# GH_Terra_pre.net
KiCad netlist of a schematic drawn in EAGLE
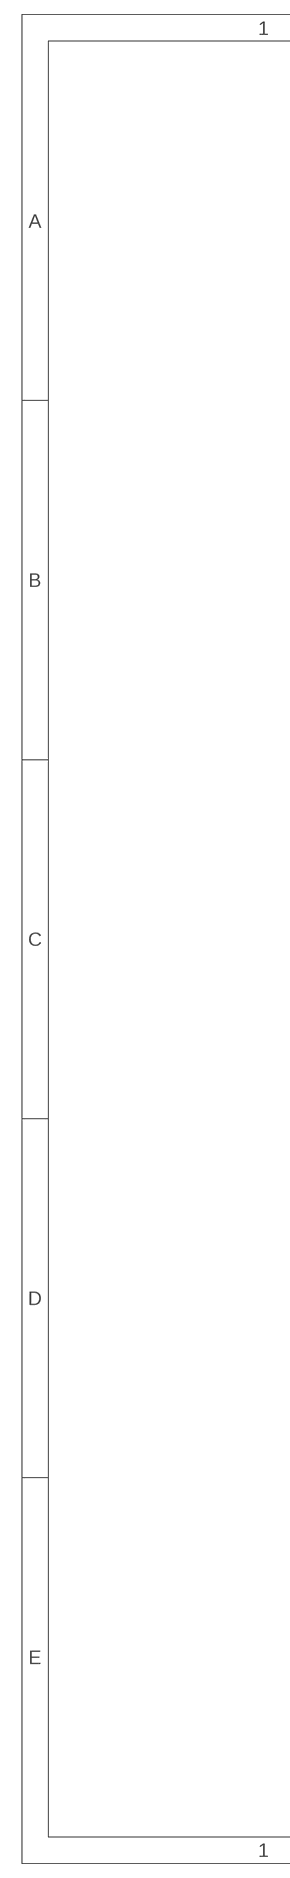
[diagram p0: schematic, sheet 1, part 1 of 2]
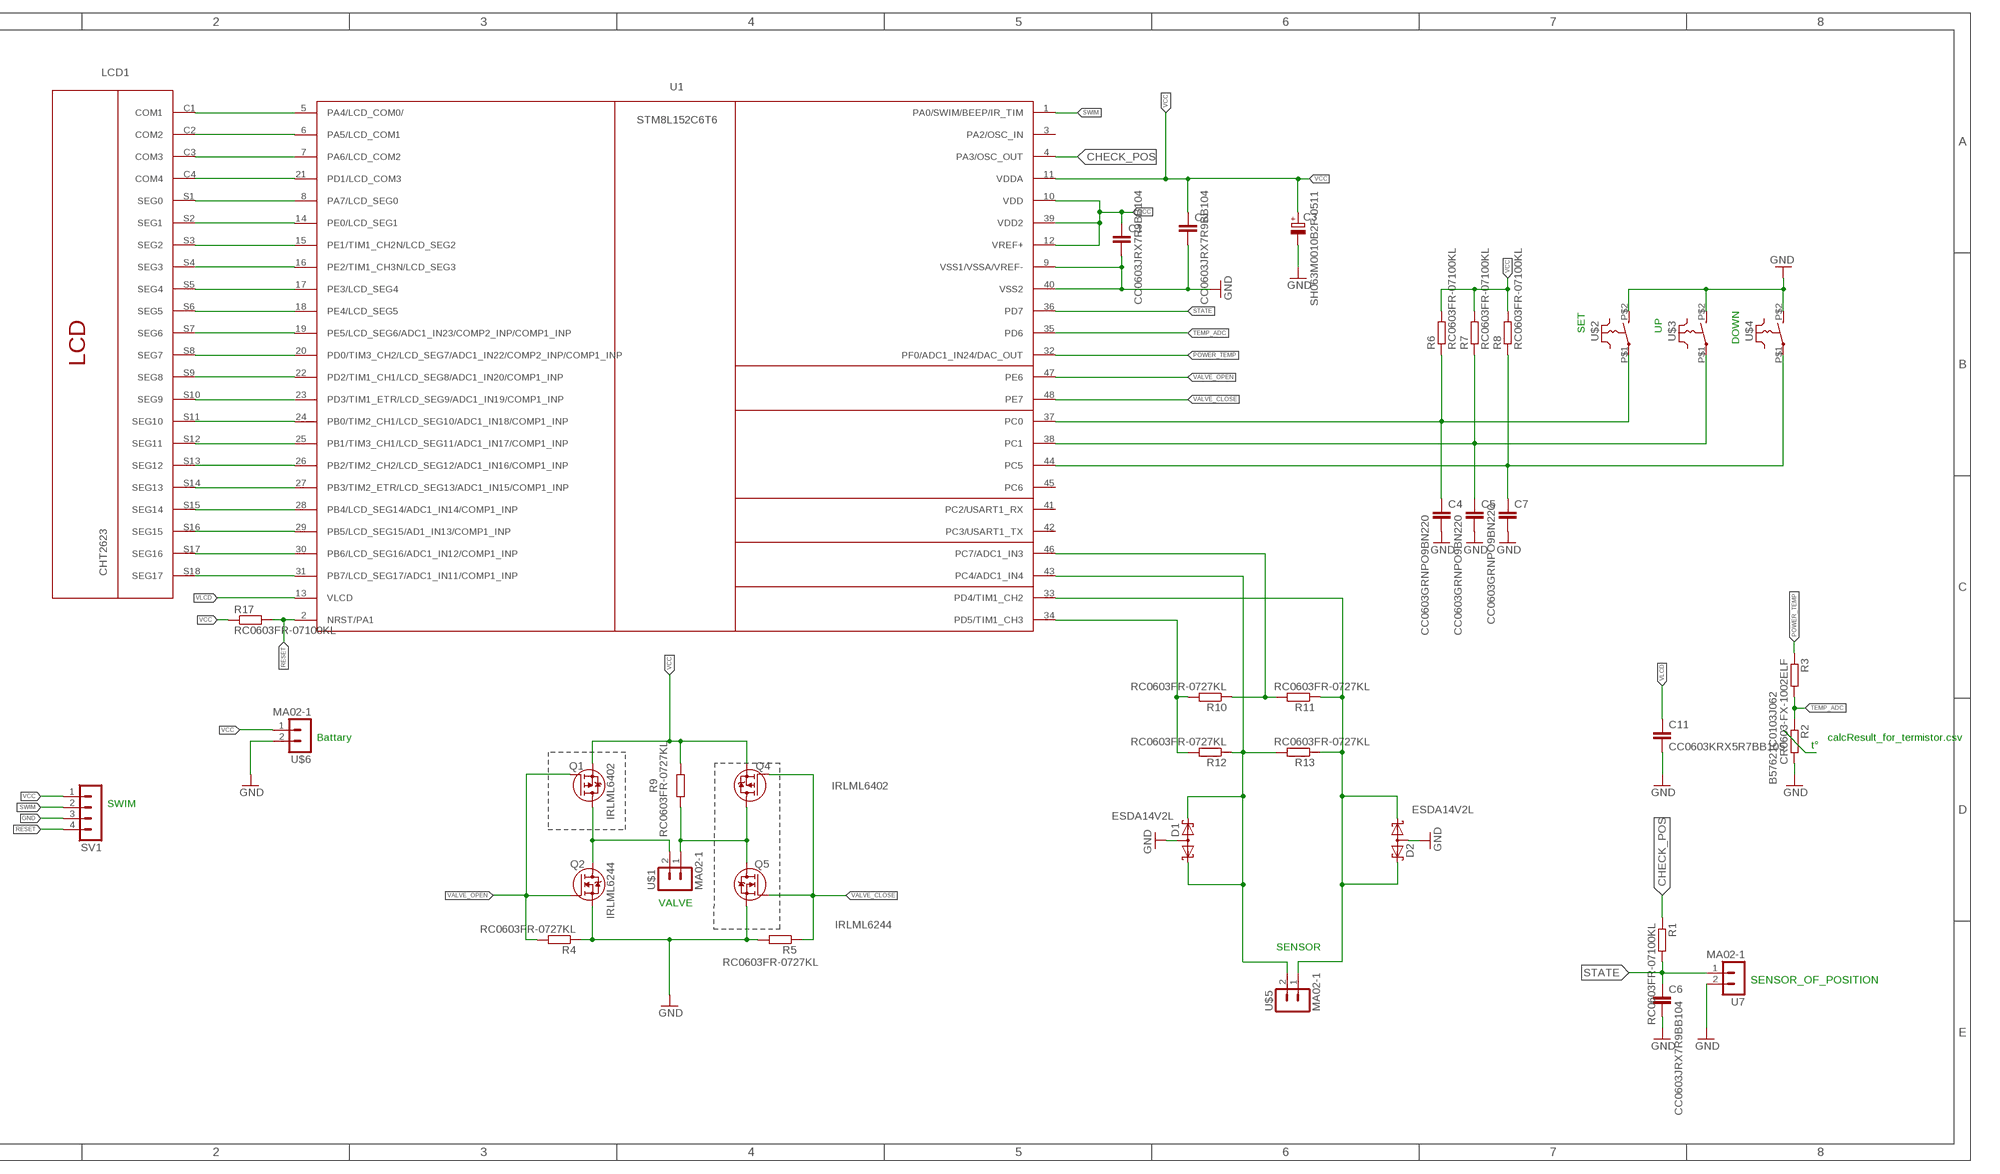
[diagram p1: schematic, sheet 1, part 2 of 2]

(export (version "E")
  (design (tool "Eeschema 10.0.6"))
  (components
    (comp (ref "C1")
      (value "CC0603JRX7R9BB104")
      (footprint "eagle-import:C0603_IPC")
      (libsource (lib "eagle-import") (part "C-EUC0603"))
    )
    (comp (ref "C2")
      (value "CC0603JRX7R9BB104")
      (footprint "eagle-import:C0603_IPC")
      (libsource (lib "eagle-import") (part "C-EUC0603"))
    )
    (comp (ref "C3")
      (value "SH063M0010B2F-0511")
      (footprint "eagle-import:SANYO-OSCON_C6")
      (libsource (lib "eagle-import") (part "CPOL-EUSANYO_C6"))
    )
    (comp (ref "C4")
      (value "CC0603GRNPO9BN220")
      (footprint "eagle-import:C0603_IPC")
      (libsource (lib "eagle-import") (part "C-EUC0603"))
    )
    (comp (ref "C5")
      (value "CC0603GRNPO9BN220")
      (footprint "eagle-import:C0603_IPC")
      (libsource (lib "eagle-import") (part "C-EUC0603"))
    )
    (comp (ref "C6")
      (value "CC0603JRX7R9BB104")
      (footprint "eagle-import:C0603_IPC")
      (libsource (lib "eagle-import") (part "C-EUC0603"))
    )
    (comp (ref "C7")
      (value "CC0603GRNPO9BN220")
      (footprint "eagle-import:C0603_IPC")
      (libsource (lib "eagle-import") (part "C-EUC0603"))
    )
    (comp (ref "C11")
      (value "CC0603KRX5R7BB105")
      (footprint "eagle-import:C0603_IPC")
      (libsource (lib "eagle-import") (part "C-EUC0603"))
    )
    (comp (ref "D1")
      (value "ESDA14V2L")
      (footprint "eagle-import:SOT23")
      (libsource (lib "eagle-import") (part "BAS40-06"))
    )
    (comp (ref "D2")
      (value "ESDA14V2L")
      (footprint "eagle-import:SOT23")
      (libsource (lib "eagle-import") (part "BAS40-06"))
    )
    (comp (ref "LCD1")
      (value "CHT2623")
      (footprint "eagle-import:CHT2623")
      (libsource (lib "eagle-import") (part "CHT2623"))
    )
    (comp (ref "Q1")
      (value "IRLML6402")
      (footprint "eagle-import:SOT23")
      (libsource (lib "eagle-import") (part "PFET-SOT23"))
    )
    (comp (ref "Q2")
      (value "IRLML6244")
      (footprint "eagle-import:SOT23")
      (libsource (lib "eagle-import") (part "NFET-SOT23"))
    )
    (comp (ref "Q4")
      (value "IRLML6402")
      (footprint "eagle-import:SOT23")
      (libsource (lib "eagle-import") (part "PFET-SOT23"))
    )
    (comp (ref "Q5")
      (value "IRLML6244")
      (footprint "eagle-import:SOT23")
      (libsource (lib "eagle-import") (part "NFET-SOT23"))
    )
    (comp (ref "R1")
      (value "RC0603FR-07100KL")
      (footprint "eagle-import:R0603_IPC")
      (libsource (lib "eagle-import") (part "R-EU_R0603"))
    )
    (comp (ref "R2")
      (value "B57621C0103J062")
      (footprint "eagle-import:R1206")
      (libsource (lib "eagle-import") (part "R-EU_R1206"))
    )
    (comp (ref "R3")
      (value "CR0603-FX-1002ELF")
      (footprint "eagle-import:R0603_IPC")
      (libsource (lib "eagle-import") (part "R-EU_R0603"))
    )
    (comp (ref "R4")
      (value "RC0603FR-0727KL")
      (footprint "eagle-import:R0603_IPC")
      (libsource (lib "eagle-import") (part "R-EU_R0603"))
    )
    (comp (ref "R5")
      (value "RC0603FR-0727KL")
      (footprint "eagle-import:R0603_IPC")
      (libsource (lib "eagle-import") (part "R-EU_R0603"))
    )
    (comp (ref "R6")
      (value "RC0603FR-07100KL")
      (footprint "eagle-import:R0603_IPC")
      (libsource (lib "eagle-import") (part "R-EU_R0603"))
    )
    (comp (ref "R7")
      (value "RC0603FR-07100KL")
      (footprint "eagle-import:R0603_IPC")
      (libsource (lib "eagle-import") (part "R-EU_R0603"))
    )
    (comp (ref "R8")
      (value "RC0603FR-07100KL")
      (footprint "eagle-import:R0603_IPC")
      (libsource (lib "eagle-import") (part "R-EU_R0603"))
    )
    (comp (ref "R9")
      (value "RC0603FR-0727KL")
      (footprint "eagle-import:R0603_IPC")
      (libsource (lib "eagle-import") (part "R-EU_R0603"))
    )
    (comp (ref "R10")
      (value "RC0603FR-0727KL")
      (footprint "eagle-import:R0603_IPC")
      (libsource (lib "eagle-import") (part "R-EU_R0603"))
    )
    (comp (ref "R11")
      (value "RC0603FR-0727KL")
      (footprint "eagle-import:R0603_IPC")
      (libsource (lib "eagle-import") (part "R-EU_R0603"))
    )
    (comp (ref "R12")
      (value "RC0603FR-0727KL")
      (footprint "eagle-import:R0603_IPC")
      (libsource (lib "eagle-import") (part "R-EU_R0603"))
    )
    (comp (ref "R13")
      (value "RC0603FR-0727KL")
      (footprint "eagle-import:R0603_IPC")
      (libsource (lib "eagle-import") (part "R-EU_R0603"))
    )
    (comp (ref "R17")
      (value "RC0603FR-07100KL")
      (footprint "eagle-import:R0603_IPC")
      (libsource (lib "eagle-import") (part "R-EU_R0603"))
    )
    (comp (ref "SV1")
      (value "MA04-1")
      (footprint "eagle-import:MA04-1")
      (libsource (lib "eagle-import") (part "MA04-1"))
    )
    (comp (ref "U$1")
      (value "MA02-1")
      (footprint "eagle-import:MA02-1")
      (libsource (lib "eagle-import") (part "MA02-1"))
    )
    (comp (ref "U$2")
      (value "RK_4X3")
      (footprint "eagle-import:RK_3X4")
      (libsource (lib "eagle-import") (part "RK_4X3"))
    )
    (comp (ref "U$3")
      (value "RK_4X3")
      (footprint "eagle-import:RK_3X4")
      (libsource (lib "eagle-import") (part "RK_4X3"))
    )
    (comp (ref "U$4")
      (value "RK_4X3")
      (footprint "eagle-import:RK_3X4")
      (libsource (lib "eagle-import") (part "RK_4X3"))
    )
    (comp (ref "U$5")
      (value "MA02-1")
      (footprint "eagle-import:MA02-1")
      (libsource (lib "eagle-import") (part "MA02-1"))
    )
    (comp (ref "U$6")
      (value "MA02-1")
      (footprint "eagle-import:MA02-1")
      (libsource (lib "eagle-import") (part "MA02-1"))
    )
    (comp (ref "U1")
      (value "STM8L152C6T6")
      (footprint "eagle-import:LQFP48")
      (libsource (lib "eagle-import") (part "STM8L152C6"))
    )
    (comp (ref "U7")
      (value "MA02-1")
      (footprint "eagle-import:MA02-1")
      (libsource (lib "eagle-import") (part "MA02-1"))
    )
  )
  (nets
    (net (code "1") (name "CHECK_POS") (class "Default")
      (node (ref "R1") (pin "1") (pinfunction "1_1") (pintype "passive"))
      (node (ref "U1") (pin "4") (pinfunction "PA3/OSC_OUT_4") (pintype "bidirectional"))
    )
    (net (code "2") (name "GND") (class "Default")
      (node (ref "C1") (pin "2") (pinfunction "2_2") (pintype "passive"))
      (node (ref "C11") (pin "2") (pinfunction "2_2") (pintype "passive"))
      (node (ref "C2") (pin "2") (pinfunction "2_2") (pintype "passive"))
      (node (ref "C3") (pin "-") (pinfunction "-_-") (pintype "passive"))
      (node (ref "C4") (pin "2") (pinfunction "2_2") (pintype "passive"))
      (node (ref "C5") (pin "2") (pinfunction "2_2") (pintype "passive"))
      (node (ref "C6") (pin "2") (pinfunction "2_2") (pintype "passive"))
      (node (ref "C7") (pin "2") (pinfunction "2_2") (pintype "passive"))
      (node (ref "D1") (pin "3") (pinfunction "AA_3") (pintype "passive"))
      (node (ref "D2") (pin "3") (pinfunction "AA_3") (pintype "passive"))
      (node (ref "Q2") (pin "2") (pinfunction "S_2") (pintype "passive"))
      (node (ref "Q5") (pin "2") (pinfunction "S_2") (pintype "passive"))
      (node (ref "R2") (pin "2") (pinfunction "2_2") (pintype "passive"))
      (node (ref "R4") (pin "1") (pinfunction "1_1") (pintype "passive"))
      (node (ref "R5") (pin "2") (pinfunction "2_2") (pintype "passive"))
      (node (ref "SV1") (pin "3") (pinfunction "3_3") (pintype "passive"))
      (node (ref "U$2") (pin "P$2") (pinfunction "S_P$2") (pintype "passive"))
      (node (ref "U$3") (pin "P$2") (pinfunction "S_P$2") (pintype "passive"))
      (node (ref "U$4") (pin "P$2") (pinfunction "S_P$2") (pintype "passive"))
      (node (ref "U$6") (pin "2") (pinfunction "2_2") (pintype "passive"))
      (node (ref "U1") (pin "40") (pinfunction "VSS2_40") (pintype "bidirectional"))
      (node (ref "U1") (pin "9") (pinfunction "VSS1/VSSA/VREF-_9") (pintype "bidirectional"))
      (node (ref "U7") (pin "2") (pinfunction "2_2") (pintype "passive"))
    )
    (net (code "3") (name "Net-(D1-K1)") (class "Default")
      (node (ref "D1") (pin "1") (pinfunction "K1_1") (pintype "passive"))
      (node (ref "D1") (pin "2") (pinfunction "K2_2") (pintype "passive"))
      (node (ref "R12") (pin "1") (pinfunction "1_1") (pintype "passive"))
      (node (ref "R13") (pin "2") (pinfunction "2_2") (pintype "passive"))
      (node (ref "U$5") (pin "2") (pinfunction "2_2") (pintype "passive"))
      (node (ref "U1") (pin "43") (pinfunction "PC4/ADC1_IN4_43") (pintype "bidirectional"))
    )
    (net (code "4") (name "Net-(D2-K1)") (class "Default")
      (node (ref "D2") (pin "1") (pinfunction "K1_1") (pintype "passive"))
      (node (ref "D2") (pin "2") (pinfunction "K2_2") (pintype "passive"))
      (node (ref "R11") (pin "1") (pinfunction "1_1") (pintype "passive"))
      (node (ref "R13") (pin "1") (pinfunction "1_1") (pintype "passive"))
      (node (ref "U$5") (pin "1") (pinfunction "1_1") (pintype "passive"))
      (node (ref "U1") (pin "33") (pinfunction "PD4/TIM1_CH2_33") (pintype "bidirectional"))
    )
    (net (code "5") (name "Net-(LCD1-COM1)") (class "Default")
      (node (ref "LCD1") (pin "C1") (pinfunction "COM1_C1") (pintype "bidirectional"))
      (node (ref "U1") (pin "5") (pinfunction "PA4/LCD_COM0/_5") (pintype "bidirectional"))
    )
    (net (code "6") (name "Net-(LCD1-COM2)") (class "Default")
      (node (ref "LCD1") (pin "C2") (pinfunction "COM2_C2") (pintype "bidirectional"))
      (node (ref "U1") (pin "6") (pinfunction "PA5/LCD_COM1_6") (pintype "bidirectional"))
    )
    (net (code "7") (name "Net-(LCD1-COM3)") (class "Default")
      (node (ref "LCD1") (pin "C3") (pinfunction "COM3_C3") (pintype "bidirectional"))
      (node (ref "U1") (pin "7") (pinfunction "PA6/LCD_COM2_7") (pintype "bidirectional"))
    )
    (net (code "8") (name "Net-(LCD1-COM4)") (class "Default")
      (node (ref "LCD1") (pin "C4") (pinfunction "COM4_C4") (pintype "bidirectional"))
      (node (ref "U1") (pin "21") (pinfunction "PD1/LCD_COM3_21") (pintype "bidirectional"))
    )
    (net (code "9") (name "Net-(LCD1-SEG0)") (class "Default")
      (node (ref "LCD1") (pin "S1") (pinfunction "SEG0_S1") (pintype "bidirectional"))
      (node (ref "U1") (pin "8") (pinfunction "PA7/LCD_SEG0_8") (pintype "bidirectional"))
    )
    (net (code "10") (name "Net-(LCD1-SEG1)") (class "Default")
      (node (ref "LCD1") (pin "S2") (pinfunction "SEG1_S2") (pintype "bidirectional"))
      (node (ref "U1") (pin "14") (pinfunction "PE0/LCD_SEG1_14") (pintype "bidirectional"))
    )
    (net (code "11") (name "Net-(LCD1-SEG2)") (class "Default")
      (node (ref "LCD1") (pin "S3") (pinfunction "SEG2_S3") (pintype "bidirectional"))
      (node (ref "U1") (pin "15") (pinfunction "PE1/TIM1_CH2N/LCD_SEG2_15") (pintype "bidirectional"))
    )
    (net (code "12") (name "Net-(LCD1-SEG3)") (class "Default")
      (node (ref "LCD1") (pin "S4") (pinfunction "SEG3_S4") (pintype "bidirectional"))
      (node (ref "U1") (pin "16") (pinfunction "PE2/TIM1_CH3N/LCD_SEG3_16") (pintype "bidirectional"))
    )
    (net (code "13") (name "Net-(LCD1-SEG4)") (class "Default")
      (node (ref "LCD1") (pin "S5") (pinfunction "SEG4_S5") (pintype "bidirectional"))
      (node (ref "U1") (pin "17") (pinfunction "PE3/LCD_SEG4_17") (pintype "bidirectional"))
    )
    (net (code "14") (name "Net-(LCD1-SEG5)") (class "Default")
      (node (ref "LCD1") (pin "S6") (pinfunction "SEG5_S6") (pintype "bidirectional"))
      (node (ref "U1") (pin "18") (pinfunction "PE4/LCD_SEG5_18") (pintype "bidirectional"))
    )
    (net (code "15") (name "Net-(LCD1-SEG6)") (class "Default")
      (node (ref "LCD1") (pin "S7") (pinfunction "SEG6_S7") (pintype "bidirectional"))
      (node (ref "U1") (pin "19") (pinfunction "PE5/LCD_SEG6/ADC1_IN23/COMP2_INP/COMP1_INP_19") (pintype "bidirectional"))
    )
    (net (code "16") (name "Net-(LCD1-SEG7)") (class "Default")
      (node (ref "LCD1") (pin "S8") (pinfunction "SEG7_S8") (pintype "bidirectional"))
      (node (ref "U1") (pin "20") (pinfunction "PD0/TIM3_CH2/LCD_SEG7/ADC1_IN22/COMP2_INP/COMP1_INP_20") (pintype "bidirectional"))
    )
    (net (code "17") (name "Net-(LCD1-SEG8)") (class "Default")
      (node (ref "LCD1") (pin "S9") (pinfunction "SEG8_S9") (pintype "bidirectional"))
      (node (ref "U1") (pin "22") (pinfunction "PD2/TIM1_CH1/LCD_SEG8/ADC1_IN20/COMP1_INP_22") (pintype "bidirectional"))
    )
    (net (code "18") (name "Net-(LCD1-SEG9)") (class "Default")
      (node (ref "LCD1") (pin "S10") (pinfunction "SEG9_S10") (pintype "bidirectional"))
      (node (ref "U1") (pin "23") (pinfunction "PD3/TIM1_ETR/LCD_SEG9/ADC1_IN19/COMP1_INP_23") (pintype "bidirectional"))
    )
    (net (code "19") (name "Net-(LCD1-SEG10)") (class "Default")
      (node (ref "LCD1") (pin "S11") (pinfunction "SEG10_S11") (pintype "bidirectional"))
      (node (ref "U1") (pin "24") (pinfunction "PB0/TIM2_CH1/LCD_SEG10/ADC1_IN18/COMP1_INP_24") (pintype "bidirectional"))
    )
    (net (code "20") (name "Net-(LCD1-SEG11)") (class "Default")
      (node (ref "LCD1") (pin "S12") (pinfunction "SEG11_S12") (pintype "bidirectional"))
      (node (ref "U1") (pin "25") (pinfunction "PB1/TIM3_CH1/LCD_SEG11/ADC1_IN17/COMP1_INP_25") (pintype "bidirectional"))
    )
    (net (code "21") (name "Net-(LCD1-SEG12)") (class "Default")
      (node (ref "LCD1") (pin "S13") (pinfunction "SEG12_S13") (pintype "bidirectional"))
      (node (ref "U1") (pin "26") (pinfunction "PB2/TIM2_CH2/LCD_SEG12/ADC1_IN16/COMP1_INP_26") (pintype "bidirectional"))
    )
    (net (code "22") (name "Net-(LCD1-SEG13)") (class "Default")
      (node (ref "LCD1") (pin "S14") (pinfunction "SEG13_S14") (pintype "bidirectional"))
      (node (ref "U1") (pin "27") (pinfunction "PB3/TIM2_ETR/LCD_SEG13/ADC1_IN15/COMP1_INP_27") (pintype "bidirectional"))
    )
    (net (code "23") (name "Net-(LCD1-SEG14)") (class "Default")
      (node (ref "LCD1") (pin "S15") (pinfunction "SEG14_S15") (pintype "bidirectional"))
      (node (ref "U1") (pin "28") (pinfunction "PB4/LCD_SEG14/ADC1_IN14/COMP1_INP_28") (pintype "bidirectional"))
    )
    (net (code "24") (name "Net-(LCD1-SEG15)") (class "Default")
      (node (ref "LCD1") (pin "S16") (pinfunction "SEG15_S16") (pintype "bidirectional"))
      (node (ref "U1") (pin "29") (pinfunction "PB5/LCD_SEG15/AD1_IN13/COMP1_INP_29") (pintype "bidirectional"))
    )
    (net (code "25") (name "Net-(LCD1-SEG16)") (class "Default")
      (node (ref "LCD1") (pin "S17") (pinfunction "SEG16_S17") (pintype "bidirectional"))
      (node (ref "U1") (pin "30") (pinfunction "PB6/LCD_SEG16/ADC1_IN12/COMP1_INP_30") (pintype "bidirectional"))
    )
    (net (code "26") (name "Net-(LCD1-SEG17)") (class "Default")
      (node (ref "LCD1") (pin "S18") (pinfunction "SEG17_S18") (pintype "bidirectional"))
      (node (ref "U1") (pin "31") (pinfunction "PB7/LCD_SEG17/ADC1_IN11/COMP1_INP_31") (pintype "bidirectional"))
    )
    (net (code "27") (name "Net-(Q1-D)") (class "Default")
      (node (ref "Q1") (pin "3") (pinfunction "D_3") (pintype "passive"))
      (node (ref "Q2") (pin "3") (pinfunction "D_3") (pintype "passive"))
      (node (ref "U$1") (pin "2") (pinfunction "2_2") (pintype "passive"))
    )
    (net (code "28") (name "Net-(Q4-D)") (class "Default")
      (node (ref "Q4") (pin "3") (pinfunction "D_3") (pintype "passive"))
      (node (ref "Q5") (pin "3") (pinfunction "D_3") (pintype "passive"))
      (node (ref "R9") (pin "2") (pinfunction "2_2") (pintype "passive"))
      (node (ref "U$1") (pin "1") (pinfunction "1_1") (pintype "passive"))
    )
    (net (code "29") (name "Net-(U$2-P)") (class "Default")
      (node (ref "C4") (pin "1") (pinfunction "1_1") (pintype "passive"))
      (node (ref "R6") (pin "1") (pinfunction "1_1") (pintype "passive"))
      (node (ref "U$2") (pin "P$1") (pinfunction "P_P$1") (pintype "passive"))
      (node (ref "U1") (pin "37") (pinfunction "PC0_37") (pintype "bidirectional"))
    )
    (net (code "30") (name "Net-(U$3-P)") (class "Default")
      (node (ref "C5") (pin "1") (pinfunction "1_1") (pintype "passive"))
      (node (ref "R7") (pin "1") (pinfunction "1_1") (pintype "passive"))
      (node (ref "U$3") (pin "P$1") (pinfunction "P_P$1") (pintype "passive"))
      (node (ref "U1") (pin "38") (pinfunction "PC1_38") (pintype "bidirectional"))
    )
    (net (code "31") (name "Net-(U$4-P)") (class "Default")
      (node (ref "C7") (pin "1") (pinfunction "1_1") (pintype "passive"))
      (node (ref "R8") (pin "1") (pinfunction "1_1") (pintype "passive"))
      (node (ref "U$4") (pin "P$1") (pinfunction "P_P$1") (pintype "passive"))
      (node (ref "U1") (pin "44") (pinfunction "PC5_44") (pintype "bidirectional"))
    )
    (net (code "32") (name "Net-(U1-PC7{slash}ADC1_IN3)") (class "Default")
      (node (ref "R10") (pin "1") (pinfunction "1_1") (pintype "passive"))
      (node (ref "R11") (pin "2") (pinfunction "2_2") (pintype "passive"))
      (node (ref "U1") (pin "46") (pinfunction "PC7/ADC1_IN3_46") (pintype "bidirectional"))
    )
    (net (code "33") (name "Net-(U1-PD5{slash}TIM1_CH3)") (class "Default")
      (node (ref "R10") (pin "2") (pinfunction "2_2") (pintype "passive"))
      (node (ref "R12") (pin "2") (pinfunction "2_2") (pintype "passive"))
      (node (ref "U1") (pin "34") (pinfunction "PD5/TIM1_CH3_34") (pintype "bidirectional"))
    )
    (net (code "34") (name "POWER_TEMP") (class "Default")
      (node (ref "R3") (pin "1") (pinfunction "1_1") (pintype "passive"))
      (node (ref "U1") (pin "32") (pinfunction "PF0/ADC1_IN24/DAC_OUT_32") (pintype "bidirectional"))
    )
    (net (code "35") (name "RESET") (class "Default")
      (node (ref "R17") (pin "2") (pinfunction "2_2") (pintype "passive"))
      (node (ref "SV1") (pin "4") (pinfunction "4_4") (pintype "passive"))
      (node (ref "U1") (pin "2") (pinfunction "NRST/PA1_2") (pintype "bidirectional"))
    )
    (net (code "36") (name "STATE") (class "Default")
      (node (ref "C6") (pin "1") (pinfunction "1_1") (pintype "passive"))
      (node (ref "R1") (pin "2") (pinfunction "2_2") (pintype "passive"))
      (node (ref "U1") (pin "36") (pinfunction "PD7_36") (pintype "bidirectional"))
      (node (ref "U7") (pin "1") (pinfunction "1_1") (pintype "passive"))
    )
    (net (code "37") (name "SWIM") (class "Default")
      (node (ref "SV1") (pin "2") (pinfunction "2_2") (pintype "passive"))
      (node (ref "U1") (pin "1") (pinfunction "PA0/SWIM/BEEP/IR_TIM_1") (pintype "bidirectional"))
    )
    (net (code "38") (name "TEMP_ADC") (class "Default")
      (node (ref "R2") (pin "1") (pinfunction "1_1") (pintype "passive"))
      (node (ref "R3") (pin "2") (pinfunction "2_2") (pintype "passive"))
      (node (ref "U1") (pin "35") (pinfunction "PD6_35") (pintype "bidirectional"))
    )
    (net (code "39") (name "VALVE_CLOSE") (class "Default")
      (node (ref "Q4") (pin "1") (pinfunction "G_1") (pintype "passive"))
      (node (ref "Q5") (pin "1") (pinfunction "G_1") (pintype "passive"))
      (node (ref "R5") (pin "1") (pinfunction "1_1") (pintype "passive"))
      (node (ref "U1") (pin "48") (pinfunction "PE7_48") (pintype "bidirectional"))
    )
    (net (code "40") (name "VALVE_OPEN") (class "Default")
      (node (ref "Q1") (pin "1") (pinfunction "G_1") (pintype "passive"))
      (node (ref "Q2") (pin "1") (pinfunction "G_1") (pintype "passive"))
      (node (ref "R4") (pin "2") (pinfunction "2_2") (pintype "passive"))
      (node (ref "U1") (pin "47") (pinfunction "PE6_47") (pintype "bidirectional"))
    )
    (net (code "41") (name "VCC") (class "Default")
      (node (ref "C1") (pin "1") (pinfunction "1_1") (pintype "passive"))
      (node (ref "C2") (pin "1") (pinfunction "1_1") (pintype "passive"))
      (node (ref "C3") (pin "+") (pinfunction "+_+") (pintype "passive"))
      (node (ref "Q1") (pin "2") (pinfunction "S_2") (pintype "passive"))
      (node (ref "Q4") (pin "2") (pinfunction "S_2") (pintype "passive"))
      (node (ref "R17") (pin "1") (pinfunction "1_1") (pintype "passive"))
      (node (ref "R6") (pin "2") (pinfunction "2_2") (pintype "passive"))
      (node (ref "R7") (pin "2") (pinfunction "2_2") (pintype "passive"))
      (node (ref "R8") (pin "2") (pinfunction "2_2") (pintype "passive"))
      (node (ref "R9") (pin "1") (pinfunction "1_1") (pintype "passive"))
      (node (ref "SV1") (pin "1") (pinfunction "1_1") (pintype "passive"))
      (node (ref "U$6") (pin "1") (pinfunction "1_1") (pintype "passive"))
      (node (ref "U1") (pin "10") (pinfunction "VDD_10") (pintype "bidirectional"))
      (node (ref "U1") (pin "11") (pinfunction "VDDA_11") (pintype "bidirectional"))
      (node (ref "U1") (pin "12") (pinfunction "VREF+_12") (pintype "bidirectional"))
      (node (ref "U1") (pin "39") (pinfunction "VDD2_39") (pintype "bidirectional"))
    )
    (net (code "42") (name "VLCD") (class "Default")
      (node (ref "C11") (pin "1") (pinfunction "1_1") (pintype "passive"))
      (node (ref "U1") (pin "13") (pinfunction "VLCD_13") (pintype "bidirectional"))
    )
    (net (code "43") (name "unconnected-(U1-PA2{slash}OSC_IN-Pad3)") (class "Default")
      (node (ref "U1") (pin "3") (pinfunction "PA2/OSC_IN_3") (pintype "bidirectional"))
    )
    (net (code "44") (name "unconnected-(U1-PC2{slash}USART1_RX-Pad41)") (class "Default")
      (node (ref "U1") (pin "41") (pinfunction "PC2/USART1_RX_41") (pintype "bidirectional"))
    )
    (net (code "45") (name "unconnected-(U1-PC3{slash}USART1_TX-Pad42)") (class "Default")
      (node (ref "U1") (pin "42") (pinfunction "PC3/USART1_TX_42") (pintype "bidirectional"))
    )
    (net (code "46") (name "unconnected-(U1-PC6-Pad45)") (class "Default")
      (node (ref "U1") (pin "45") (pinfunction "PC6_45") (pintype "bidirectional"))
    )
  )
)
